# 8_RTC.net
KiCad netlist of a schematic drawn in Altium Designer
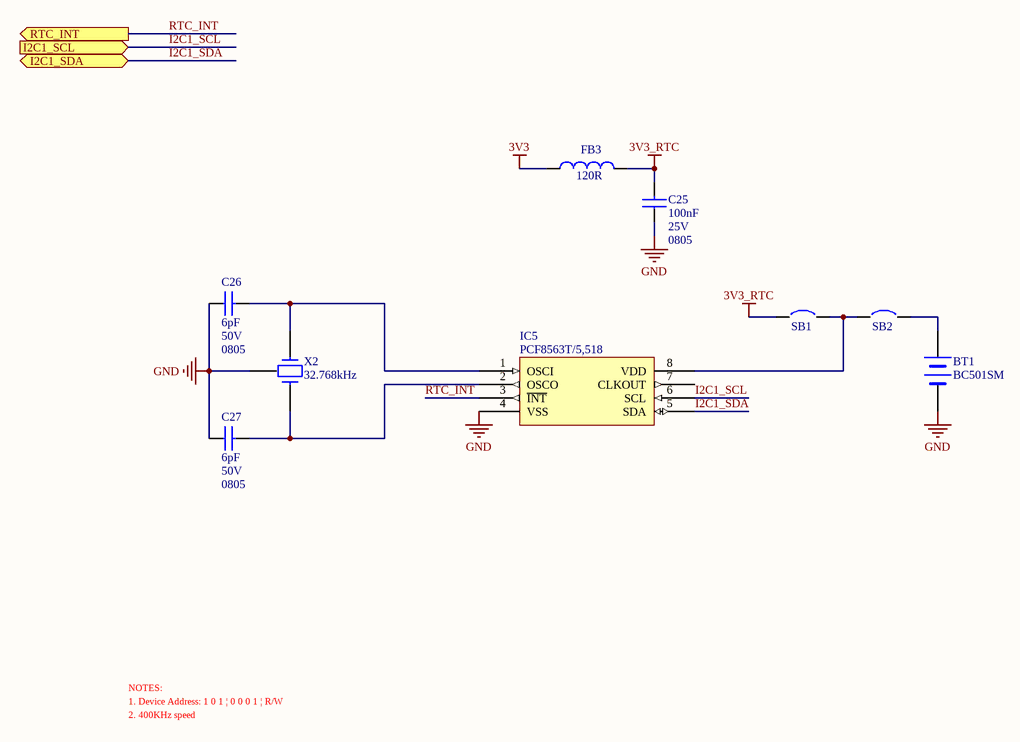
[diagram p0: 8.RTC.SchDoc]

(export (version "E")
  (design (tool "Eeschema 10.0.6"))
  (components
    (comp (ref "BT1")
      (value "BC501SM")
      (footprint "MPD_BC501SM")
      (description "HOLDER COIN CELL FOR CR1220 SMD")
      (fields (field (name "PART NUMBER") "SBAT00011") (field (name "VOLTAGE") "3V"))
      (libsource (lib "ComponentDatabase") (part "BATTERY"))
    )
    (comp (ref "C25")
      (value "CAP_NP")
      (footprint "CAPC2012X100N_EIA0805")
      (description "CAP CER 0.1UF 25V X7R 0805")
      (fields
        (field (name "PART NUMBER") "SCAP00300093")
        (field (name "CAPACITANCE") "100nF")
        (field (name "TOLERANCE") "±10%")
        (field (name "VOLTAGE - RATED") "25V")
        (field (name "PACKAGE / CASE") "0805")
      )
      (libsource (lib "ComponentDatabase") (part "CAP_NP"))
    )
    (comp (ref "C26")
      (value "CAP_NP")
      (footprint "CAPC2012X100N_EIA0805")
      (description "CAP CER 6PF 50V NP0 0805")
      (fields
        (field (name "PART NUMBER") "SCAP00300025")
        (field (name "CAPACITANCE") "6pF")
        (field (name "TOLERANCE") "±0.25pF")
        (field (name "VOLTAGE - RATED") "50V")
        (field (name "PACKAGE / CASE") "0805")
      )
      (libsource (lib "ComponentDatabase") (part "CAP_NP"))
    )
    (comp (ref "C27")
      (value "CAP_NP")
      (footprint "CAPC2012X100N_EIA0805")
      (description "CAP CER 6PF 50V NP0 0805")
      (fields
        (field (name "PART NUMBER") "SCAP00300025")
        (field (name "CAPACITANCE") "6pF")
        (field (name "TOLERANCE") "±0.25pF")
        (field (name "VOLTAGE - RATED") "50V")
        (field (name "PACKAGE / CASE") "0805")
      )
      (libsource (lib "ComponentDatabase") (part "CAP_NP"))
    )
    (comp (ref "FB3")
      (value "BEAD")
      (footprint "FILC2012X100N_EIA0805")
      (description "FERRITE CHIP POWER 120 OHM SMD")
      (fields
        (field (name "PART NUMBER") "SFIL00005")
        (field (name "IMPEDANCE") "120R")
        (field (name "MANUFACTURER") "Laird-Signal Integrity Products")
      )
      (libsource (lib "ComponentDatabase") (part "BEAD"))
    )
    (comp (ref "IC5")
      (value "PC58563")
      (footprint "SOIC127P600X175-8N")
      (description "IC RTC CLK/CALENDAR I2C 8-SOIC")
      (fields
        (field (name "PART NUMBER") "SIC00132")
        (field (name "MANUFACTURER PART NUMBER") "PCF8563T/5,518")
        (field (name "MANUFACTURER") "NXP Semiconductors")
      )
      (libsource (lib "ComponentDatabase") (part "PC58563"))
    )
    (comp (ref "SB1")
      (value "SOLDER_BRIDGE")
      (footprint "SOLDER_BRIDGE_0805")
      (description "SOLDER BRIDGE 0805")
      (fields (field (name "PART NUMBER") "SMSC00006"))
      (libsource (lib "ComponentDatabase") (part "SOLDER_BRIDGE"))
    )
    (comp (ref "SB2")
      (value "SOLDER_BRIDGE")
      (footprint "SOLDER_BRIDGE_0805")
      (description "SOLDER BRIDGE 0805")
      (fields (field (name "PART NUMBER") "SMSC00006"))
      (libsource (lib "ComponentDatabase") (part "SOLDER_BRIDGE"))
    )
    (comp (ref "X2")
      (value "32.768kHz")
      (footprint "32.768_DIP")
      (description "CRYSTAL 32.768KHZ 6PF THRU")
      (fields (field (name "PART NUMBER") "SCRY00009") (field (name "MANUFACTURER") "Seiko Instruments"))
      (libsource (lib "ComponentDatabase") (part "CRYSTAL_32K"))
    )
  )
  (nets
    (net (code "1") (name "/I2C1_SCL") (class "Default")
      (node (ref "IC5") (pin "6") (pinfunction "SCL_6") (pintype "input"))
    )
    (net (code "2") (name "/I2C1_SDA") (class "Default")
      (node (ref "IC5") (pin "5") (pinfunction "SDA_5") (pintype "bidirectional"))
    )
    (net (code "3") (name "/RTC_INT") (class "Default")
      (node (ref "IC5") (pin "3") (pinfunction "~{INT}_3") (pintype "output"))
    )
    (net (code "4") (name "3V3") (class "Default")
      (node (ref "FB3") (pin "1") (pinfunction "1_1") (pintype "passive"))
    )
    (net (code "5") (name "3V3_RTC") (class "Default")
      (node (ref "C25") (pin "2") (pinfunction "2_2") (pintype "passive"))
      (node (ref "FB3") (pin "2") (pinfunction "2_2") (pintype "passive"))
      (node (ref "SB1") (pin "1") (pinfunction "1_1") (pintype "passive"))
    )
    (net (code "6") (name "GND") (class "Default")
      (node (ref "BT1") (pin "2") (pinfunction "-_2") (pintype "passive"))
      (node (ref "C25") (pin "1") (pinfunction "1_1") (pintype "passive"))
      (node (ref "C26") (pin "1") (pinfunction "1_1") (pintype "passive"))
      (node (ref "C27") (pin "1") (pinfunction "1_1") (pintype "passive"))
      (node (ref "IC5") (pin "4") (pinfunction "VSS_4") (pintype "power_in"))
      (node (ref "X2") (pin "3") (pinfunction "3_3") (pintype "power_in"))
    )
    (net (code "7") (name "Net-(BT1-+)") (class "Default")
      (node (ref "BT1") (pin "1") (pinfunction "+_1") (pintype "passive"))
      (node (ref "SB2") (pin "2") (pinfunction "2_2") (pintype "passive"))
    )
    (net (code "8") (name "Net-(IC5-OSCI)") (class "Default")
      (node (ref "C26") (pin "2") (pinfunction "2_2") (pintype "passive"))
      (node (ref "IC5") (pin "1") (pinfunction "OSCI_1") (pintype "input"))
      (node (ref "X2") (pin "2") (pinfunction "2_2") (pintype "passive"))
    )
    (net (code "9") (name "Net-(IC5-OSCO)") (class "Default")
      (node (ref "C27") (pin "2") (pinfunction "2_2") (pintype "passive"))
      (node (ref "IC5") (pin "2") (pinfunction "OSCO_2") (pintype "output"))
      (node (ref "X2") (pin "1") (pinfunction "1_1") (pintype "passive"))
    )
    (net (code "10") (name "Net-(IC5-VDD)") (class "Default")
      (node (ref "IC5") (pin "8") (pinfunction "VDD_8") (pintype "power_in"))
      (node (ref "SB1") (pin "2") (pinfunction "2_2") (pintype "passive"))
      (node (ref "SB2") (pin "1") (pinfunction "1_1") (pintype "passive"))
    )
    (net (code "11") (name "unconnected-(IC5-CLKOUT-Pad7)") (class "Default")
      (node (ref "IC5") (pin "7") (pinfunction "CLKOUT_7") (pintype "output"))
    )
  )
)
